# Electrics.net
KiCad netlist of a schematic drawn in EAGLE
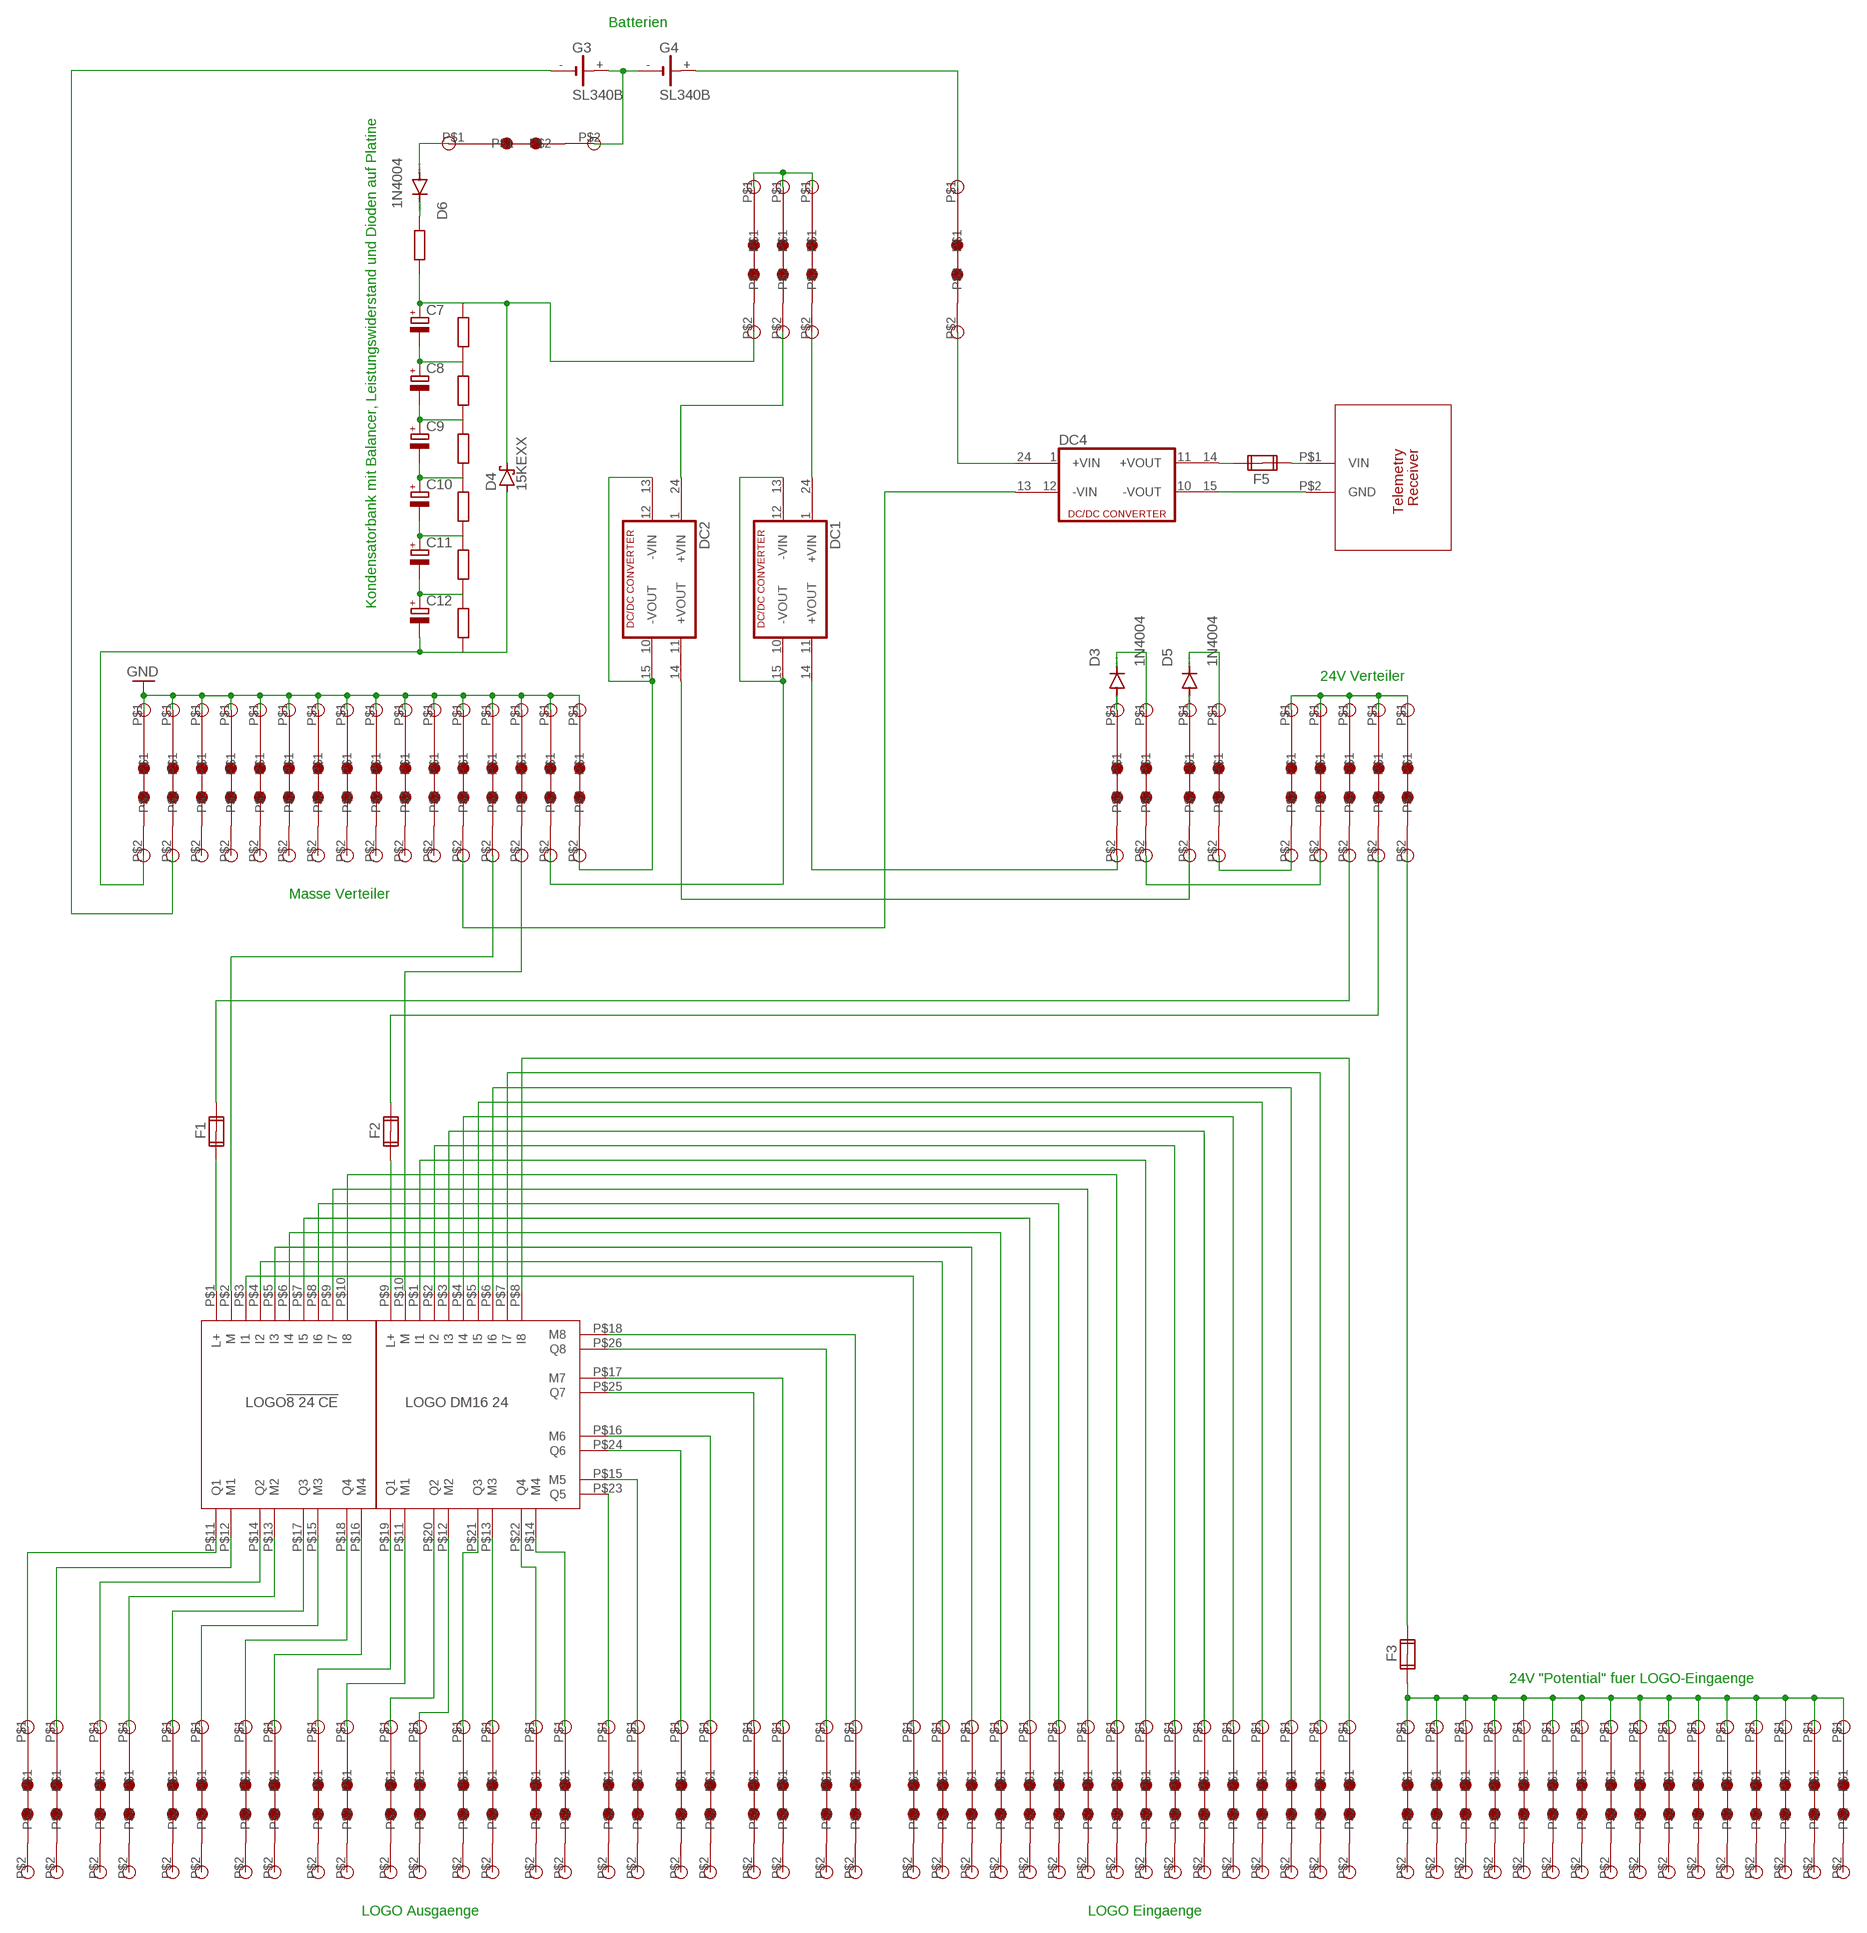
[diagram p0: schematic, sheet 1]

(export (version "E")
  (design (tool "Eeschema 10.0.6"))
  (components
    (comp (ref "C7")
      (value "CPOL-EU085CS-1AR")
      (footprint "eagle-import:085CS_1AR")
      (libsource (lib "eagle-import") (part "CPOL-EU085CS-1AR"))
    )
    (comp (ref "C8")
      (value "CPOL-EU085CS-1AR")
      (footprint "eagle-import:085CS_1AR")
      (libsource (lib "eagle-import") (part "CPOL-EU085CS-1AR"))
    )
    (comp (ref "C9")
      (value "CPOL-EU085CS-1AR")
      (footprint "eagle-import:085CS_1AR")
      (libsource (lib "eagle-import") (part "CPOL-EU085CS-1AR"))
    )
    (comp (ref "C10")
      (value "CPOL-EU085CS-1AR")
      (footprint "eagle-import:085CS_1AR")
      (libsource (lib "eagle-import") (part "CPOL-EU085CS-1AR"))
    )
    (comp (ref "C11")
      (value "CPOL-EU085CS-1AR")
      (footprint "eagle-import:085CS_1AR")
      (libsource (lib "eagle-import") (part "CPOL-EU085CS-1AR"))
    )
    (comp (ref "C12")
      (value "CPOL-EU085CS-1AR")
      (footprint "eagle-import:085CS_1AR")
      (libsource (lib "eagle-import") (part "CPOL-EU085CS-1AR"))
    )
    (comp (ref "D3")
      (value "1N4004")
      (footprint "eagle-import:DO41-10")
      (libsource (lib "eagle-import") (part "1N4004"))
    )
    (comp (ref "D4")
      (value "15KEXX")
      (footprint "eagle-import:CB429-17")
      (libsource (lib "eagle-import") (part "15KEXX"))
    )
    (comp (ref "D5")
      (value "1N4004")
      (footprint "eagle-import:DO41-10")
      (libsource (lib "eagle-import") (part "1N4004"))
    )
    (comp (ref "D6")
      (value "1N4004")
      (footprint "eagle-import:DO41-10")
      (libsource (lib "eagle-import") (part "1N4004"))
    )
    (comp (ref "DC1")
      (value "DC213R")
      (footprint "eagle-import:CMK")
      (libsource (lib "eagle-import") (part "DC213R"))
    )
    (comp (ref "DC2")
      (value "DC213R")
      (footprint "eagle-import:CMK")
      (libsource (lib "eagle-import") (part "DC213R"))
    )
    (comp (ref "DC4")
      (value "DC213R")
      (footprint "eagle-import:CMK")
      (libsource (lib "eagle-import") (part "DC213R"))
    )
    (comp (ref "F1")
      (value "FUSE2P")
      (footprint "eagle-import:FUSE1")
      (libsource (lib "eagle-import") (part "FUSE2P"))
    )
    (comp (ref "F2")
      (value "FUSE2P")
      (footprint "eagle-import:FUSE1")
      (libsource (lib "eagle-import") (part "FUSE2P"))
    )
    (comp (ref "F3")
      (value "FUSE2P")
      (footprint "eagle-import:FUSE1")
      (libsource (lib "eagle-import") (part "FUSE2P"))
    )
    (comp (ref "F5")
      (value "FUSE2P")
      (footprint "eagle-import:FUSE1")
      (libsource (lib "eagle-import") (part "FUSE2P"))
    )
    (comp (ref "G3")
      (value "SL340B")
      (footprint "eagle-import:SL-340_B3.6V")
      (libsource (lib "eagle-import") (part "SL340B"))
    )
    (comp (ref "G4")
      (value "SL340B")
      (footprint "eagle-import:SL-340_B3.6V")
      (libsource (lib "eagle-import") (part "SL340B"))
    )
    (comp (ref "U$1")
      (value "2_PIN_CONNENCTOR")
      (footprint "eagle-import:2_PIN_CONN")
      (libsource (lib "eagle-import") (part "2_PIN_CONNENCTOR"))
    )
    (comp (ref "U$2")
      (value "2_PIN_CONNENCTOR")
      (footprint "eagle-import:2_PIN_CONN")
      (libsource (lib "eagle-import") (part "2_PIN_CONNENCTOR"))
    )
    (comp (ref "U$3")
      (value "2_PIN_CONNENCTOR")
      (footprint "eagle-import:2_PIN_CONN")
      (libsource (lib "eagle-import") (part "2_PIN_CONNENCTOR"))
    )
    (comp (ref "U$4")
      (value "2_PIN_CONNENCTOR")
      (footprint "eagle-import:2_PIN_CONN")
      (libsource (lib "eagle-import") (part "2_PIN_CONNENCTOR"))
    )
    (comp (ref "U$5")
      (value "LOGO8_24_CE")
      (footprint "eagle-import:LOGO8_24_CE")
      (libsource (lib "eagle-import") (part "LOGO8_24_CE"))
    )
    (comp (ref "U$7")
      (value "LOGO_DM16_24")
      (footprint "eagle-import:LOGO_DM16_24")
      (libsource (lib "eagle-import") (part "LOGO_DM16_24"))
    )
    (comp (ref "U$8")
      (value "2_PIN_CONNENCTOR")
      (footprint "eagle-import:2_PIN_CONN")
      (libsource (lib "eagle-import") (part "2_PIN_CONNENCTOR"))
    )
    (comp (ref "U$9")
      (value "2_PIN_CONNENCTOR")
      (footprint "eagle-import:2_PIN_CONN")
      (libsource (lib "eagle-import") (part "2_PIN_CONNENCTOR"))
    )
    (comp (ref "U$10")
      (value "2_PIN_CONNENCTOR")
      (footprint "eagle-import:2_PIN_CONN")
      (libsource (lib "eagle-import") (part "2_PIN_CONNENCTOR"))
    )
    (comp (ref "U$11")
      (value "2_PIN_CONNENCTOR")
      (footprint "eagle-import:2_PIN_CONN")
      (libsource (lib "eagle-import") (part "2_PIN_CONNENCTOR"))
    )
    (comp (ref "U$12")
      (value "2_PIN_CONNENCTOR")
      (footprint "eagle-import:2_PIN_CONN")
      (libsource (lib "eagle-import") (part "2_PIN_CONNENCTOR"))
    )
    (comp (ref "U$13")
      (value "2_PIN_CONNENCTOR")
      (footprint "eagle-import:2_PIN_CONN")
      (libsource (lib "eagle-import") (part "2_PIN_CONNENCTOR"))
    )
    (comp (ref "U$14")
      (value "2_PIN_CONNENCTOR")
      (footprint "eagle-import:2_PIN_CONN")
      (libsource (lib "eagle-import") (part "2_PIN_CONNENCTOR"))
    )
    (comp (ref "U$15")
      (value "2_PIN_CONNENCTOR")
      (footprint "eagle-import:2_PIN_CONN")
      (libsource (lib "eagle-import") (part "2_PIN_CONNENCTOR"))
    )
    (comp (ref "U$16")
      (value "2_PIN_CONNENCTOR")
      (footprint "eagle-import:2_PIN_CONN")
      (libsource (lib "eagle-import") (part "2_PIN_CONNENCTOR"))
    )
    (comp (ref "U$17")
      (value "2_PIN_CONNENCTOR")
      (footprint "eagle-import:2_PIN_CONN")
      (libsource (lib "eagle-import") (part "2_PIN_CONNENCTOR"))
    )
    (comp (ref "U$18")
      (value "2_PIN_CONNENCTOR")
      (footprint "eagle-import:2_PIN_CONN")
      (libsource (lib "eagle-import") (part "2_PIN_CONNENCTOR"))
    )
    (comp (ref "U$19")
      (value "2_PIN_CONNENCTOR")
      (footprint "eagle-import:2_PIN_CONN")
      (libsource (lib "eagle-import") (part "2_PIN_CONNENCTOR"))
    )
    (comp (ref "U$20")
      (value "2_PIN_CONNENCTOR")
      (footprint "eagle-import:2_PIN_CONN")
      (libsource (lib "eagle-import") (part "2_PIN_CONNENCTOR"))
    )
    (comp (ref "U$21")
      (value "2_PIN_CONNENCTOR")
      (footprint "eagle-import:2_PIN_CONN")
      (libsource (lib "eagle-import") (part "2_PIN_CONNENCTOR"))
    )
    (comp (ref "U$22")
      (value "2_PIN_CONNENCTOR")
      (footprint "eagle-import:2_PIN_CONN")
      (libsource (lib "eagle-import") (part "2_PIN_CONNENCTOR"))
    )
    (comp (ref "U$23")
      (value "2_PIN_CONNENCTOR")
      (footprint "eagle-import:2_PIN_CONN")
      (libsource (lib "eagle-import") (part "2_PIN_CONNENCTOR"))
    )
    (comp (ref "U$24")
      (value "2_PIN_CONNENCTOR")
      (footprint "eagle-import:2_PIN_CONN")
      (libsource (lib "eagle-import") (part "2_PIN_CONNENCTOR"))
    )
    (comp (ref "U$25")
      (value "2_PIN_CONNENCTOR")
      (footprint "eagle-import:2_PIN_CONN")
      (libsource (lib "eagle-import") (part "2_PIN_CONNENCTOR"))
    )
    (comp (ref "U$26")
      (value "2_PIN_CONNENCTOR")
      (footprint "eagle-import:2_PIN_CONN")
      (libsource (lib "eagle-import") (part "2_PIN_CONNENCTOR"))
    )
    (comp (ref "U$27")
      (value "2_PIN_CONNENCTOR")
      (footprint "eagle-import:2_PIN_CONN")
      (libsource (lib "eagle-import") (part "2_PIN_CONNENCTOR"))
    )
    (comp (ref "U$28")
      (value "2_PIN_CONNENCTOR")
      (footprint "eagle-import:2_PIN_CONN")
      (libsource (lib "eagle-import") (part "2_PIN_CONNENCTOR"))
    )
    (comp (ref "U$29")
      (value "2_PIN_CONNENCTOR")
      (footprint "eagle-import:2_PIN_CONN")
      (libsource (lib "eagle-import") (part "2_PIN_CONNENCTOR"))
    )
    (comp (ref "U$30")
      (value "2_PIN_CONNENCTOR")
      (footprint "eagle-import:2_PIN_CONN")
      (libsource (lib "eagle-import") (part "2_PIN_CONNENCTOR"))
    )
    (comp (ref "U$31")
      (value "2_PIN_CONNENCTOR")
      (footprint "eagle-import:2_PIN_CONN")
      (libsource (lib "eagle-import") (part "2_PIN_CONNENCTOR"))
    )
    (comp (ref "U$32")
      (value "2_PIN_CONNENCTOR")
      (footprint "eagle-import:2_PIN_CONN")
      (libsource (lib "eagle-import") (part "2_PIN_CONNENCTOR"))
    )
    (comp (ref "U$33")
      (value "2_PIN_CONNENCTOR")
      (footprint "eagle-import:2_PIN_CONN")
      (libsource (lib "eagle-import") (part "2_PIN_CONNENCTOR"))
    )
    (comp (ref "U$34")
      (value "2_PIN_CONNENCTOR")
      (footprint "eagle-import:2_PIN_CONN")
      (libsource (lib "eagle-import") (part "2_PIN_CONNENCTOR"))
    )
    (comp (ref "U$35")
      (value "2_PIN_CONNENCTOR")
      (footprint "eagle-import:2_PIN_CONN")
      (libsource (lib "eagle-import") (part "2_PIN_CONNENCTOR"))
    )
    (comp (ref "U$36")
      (value "2_PIN_CONNENCTOR")
      (footprint "eagle-import:2_PIN_CONN")
      (libsource (lib "eagle-import") (part "2_PIN_CONNENCTOR"))
    )
    (comp (ref "U$37")
      (value "2_PIN_CONNENCTOR")
      (footprint "eagle-import:2_PIN_CONN")
      (libsource (lib "eagle-import") (part "2_PIN_CONNENCTOR"))
    )
    (comp (ref "U$38")
      (value "2_PIN_CONNENCTOR")
      (footprint "eagle-import:2_PIN_CONN")
      (libsource (lib "eagle-import") (part "2_PIN_CONNENCTOR"))
    )
    (comp (ref "U$39")
      (value "2_PIN_CONNENCTOR")
      (footprint "eagle-import:2_PIN_CONN")
      (libsource (lib "eagle-import") (part "2_PIN_CONNENCTOR"))
    )
    (comp (ref "U$40")
      (value "2_PIN_CONNENCTOR")
      (footprint "eagle-import:2_PIN_CONN")
      (libsource (lib "eagle-import") (part "2_PIN_CONNENCTOR"))
    )
    (comp (ref "U$41")
      (value "2_PIN_CONNENCTOR")
      (footprint "eagle-import:2_PIN_CONN")
      (libsource (lib "eagle-import") (part "2_PIN_CONNENCTOR"))
    )
    (comp (ref "U$42")
      (value "2_PIN_CONNENCTOR")
      (footprint "eagle-import:2_PIN_CONN")
      (libsource (lib "eagle-import") (part "2_PIN_CONNENCTOR"))
    )
    (comp (ref "U$43")
      (value "2_PIN_CONNENCTOR")
      (footprint "eagle-import:2_PIN_CONN")
      (libsource (lib "eagle-import") (part "2_PIN_CONNENCTOR"))
    )
    (comp (ref "U$44")
      (value "2_PIN_CONNENCTOR")
      (footprint "eagle-import:2_PIN_CONN")
      (libsource (lib "eagle-import") (part "2_PIN_CONNENCTOR"))
    )
    (comp (ref "U$45")
      (value "2_PIN_CONNENCTOR")
      (footprint "eagle-import:2_PIN_CONN")
      (libsource (lib "eagle-import") (part "2_PIN_CONNENCTOR"))
    )
    (comp (ref "U$46")
      (value "2_PIN_CONNENCTOR")
      (footprint "eagle-import:2_PIN_CONN")
      (libsource (lib "eagle-import") (part "2_PIN_CONNENCTOR"))
    )
    (comp (ref "U$47")
      (value "2_PIN_CONNENCTOR")
      (footprint "eagle-import:2_PIN_CONN")
      (libsource (lib "eagle-import") (part "2_PIN_CONNENCTOR"))
    )
    (comp (ref "U$48")
      (value "2_PIN_CONNENCTOR")
      (footprint "eagle-import:2_PIN_CONN")
      (libsource (lib "eagle-import") (part "2_PIN_CONNENCTOR"))
    )
    (comp (ref "U$49")
      (value "2_PIN_CONNENCTOR")
      (footprint "eagle-import:2_PIN_CONN")
      (libsource (lib "eagle-import") (part "2_PIN_CONNENCTOR"))
    )
    (comp (ref "U$50")
      (value "2_PIN_CONNENCTOR")
      (footprint "eagle-import:2_PIN_CONN")
      (libsource (lib "eagle-import") (part "2_PIN_CONNENCTOR"))
    )
    (comp (ref "U$51")
      (value "2_PIN_CONNENCTOR")
      (footprint "eagle-import:2_PIN_CONN")
      (libsource (lib "eagle-import") (part "2_PIN_CONNENCTOR"))
    )
    (comp (ref "U$52")
      (value "2_PIN_CONNENCTOR")
      (footprint "eagle-import:2_PIN_CONN")
      (libsource (lib "eagle-import") (part "2_PIN_CONNENCTOR"))
    )
    (comp (ref "U$53")
      (value "2_PIN_CONNENCTOR")
      (footprint "eagle-import:2_PIN_CONN")
      (libsource (lib "eagle-import") (part "2_PIN_CONNENCTOR"))
    )
    (comp (ref "U$54")
      (value "2_PIN_CONNENCTOR")
      (footprint "eagle-import:2_PIN_CONN")
      (libsource (lib "eagle-import") (part "2_PIN_CONNENCTOR"))
    )
    (comp (ref "U$55")
      (value "2_PIN_CONNENCTOR")
      (footprint "eagle-import:2_PIN_CONN")
      (libsource (lib "eagle-import") (part "2_PIN_CONNENCTOR"))
    )
    (comp (ref "U$56")
      (value "2_PIN_CONNENCTOR")
      (footprint "eagle-import:2_PIN_CONN")
      (libsource (lib "eagle-import") (part "2_PIN_CONNENCTOR"))
    )
    (comp (ref "U$57")
      (value "2_PIN_CONNENCTOR")
      (footprint "eagle-import:2_PIN_CONN")
      (libsource (lib "eagle-import") (part "2_PIN_CONNENCTOR"))
    )
    (comp (ref "U$58")
      (value "2_PIN_CONNENCTOR")
      (footprint "eagle-import:2_PIN_CONN")
      (libsource (lib "eagle-import") (part "2_PIN_CONNENCTOR"))
    )
    (comp (ref "U$59")
      (value "2_PIN_CONNENCTOR")
      (footprint "eagle-import:2_PIN_CONN")
      (libsource (lib "eagle-import") (part "2_PIN_CONNENCTOR"))
    )
    (comp (ref "U$60")
      (value "2_PIN_CONNENCTOR")
      (footprint "eagle-import:2_PIN_CONN")
      (libsource (lib "eagle-import") (part "2_PIN_CONNENCTOR"))
    )
    (comp (ref "U$61")
      (value "2_PIN_CONNENCTOR")
      (footprint "eagle-import:2_PIN_CONN")
      (libsource (lib "eagle-import") (part "2_PIN_CONNENCTOR"))
    )
    (comp (ref "U$62")
      (value "2_PIN_CONNENCTOR")
      (footprint "eagle-import:2_PIN_CONN")
      (libsource (lib "eagle-import") (part "2_PIN_CONNENCTOR"))
    )
    (comp (ref "U$63")
      (value "2_PIN_CONNENCTOR")
      (footprint "eagle-import:2_PIN_CONN")
      (libsource (lib "eagle-import") (part "2_PIN_CONNENCTOR"))
    )
    (comp (ref "U$64")
      (value "2_PIN_CONNENCTOR")
      (footprint "eagle-import:2_PIN_CONN")
      (libsource (lib "eagle-import") (part "2_PIN_CONNENCTOR"))
    )
    (comp (ref "U$65")
      (value "2_PIN_CONNENCTOR")
      (footprint "eagle-import:2_PIN_CONN")
      (libsource (lib "eagle-import") (part "2_PIN_CONNENCTOR"))
    )
    (comp (ref "U$66")
      (value "2_PIN_CONNENCTOR")
      (footprint "eagle-import:2_PIN_CONN")
      (libsource (lib "eagle-import") (part "2_PIN_CONNENCTOR"))
    )
    (comp (ref "U$67")
      (value "2_PIN_CONNENCTOR")
      (footprint "eagle-import:2_PIN_CONN")
      (libsource (lib "eagle-import") (part "2_PIN_CONNENCTOR"))
    )
    (comp (ref "U$68")
      (value "2_PIN_CONNENCTOR")
      (footprint "eagle-import:2_PIN_CONN")
      (libsource (lib "eagle-import") (part "2_PIN_CONNENCTOR"))
    )
    (comp (ref "U$69")
      (value "2_PIN_CONNENCTOR")
      (footprint "eagle-import:2_PIN_CONN")
      (libsource (lib "eagle-import") (part "2_PIN_CONNENCTOR"))
    )
    (comp (ref "U$70")
      (value "2_PIN_CONNENCTOR")
      (footprint "eagle-import:2_PIN_CONN")
      (libsource (lib "eagle-import") (part "2_PIN_CONNENCTOR"))
    )
    (comp (ref "U$71")
      (value "2_PIN_CONNENCTOR")
      (footprint "eagle-import:2_PIN_CONN")
      (libsource (lib "eagle-import") (part "2_PIN_CONNENCTOR"))
    )
    (comp (ref "U$72")
      (value "2_PIN_CONNENCTOR")
      (footprint "eagle-import:2_PIN_CONN")
      (libsource (lib "eagle-import") (part "2_PIN_CONNENCTOR"))
    )
    (comp (ref "U$73")
      (value "2_PIN_CONNENCTOR")
      (footprint "eagle-import:2_PIN_CONN")
      (libsource (lib "eagle-import") (part "2_PIN_CONNENCTOR"))
    )
    (comp (ref "U$74")
      (value "2_PIN_CONNENCTOR")
      (footprint "eagle-import:2_PIN_CONN")
      (libsource (lib "eagle-import") (part "2_PIN_CONNENCTOR"))
    )
    (comp (ref "U$75")
      (value "2_PIN_CONNENCTOR")
      (footprint "eagle-import:2_PIN_CONN")
      (libsource (lib "eagle-import") (part "2_PIN_CONNENCTOR"))
    )
    (comp (ref "U$76")
      (value "2_PIN_CONNENCTOR")
      (footprint "eagle-import:2_PIN_CONN")
      (libsource (lib "eagle-import") (part "2_PIN_CONNENCTOR"))
    )
    (comp (ref "U$77")
      (value "2_PIN_CONNENCTOR")
      (footprint "eagle-import:2_PIN_CONN")
      (libsource (lib "eagle-import") (part "2_PIN_CONNENCTOR"))
    )
    (comp (ref "U$78")
      (value "2_PIN_CONNENCTOR")
      (footprint "eagle-import:2_PIN_CONN")
      (libsource (lib "eagle-import") (part "2_PIN_CONNENCTOR"))
    )
    (comp (ref "U$79")
      (value "2_PIN_CONNENCTOR")
      (footprint "eagle-import:2_PIN_CONN")
      (libsource (lib "eagle-import") (part "2_PIN_CONNENCTOR"))
    )
    (comp (ref "U$80")
      (value "2_PIN_CONNENCTOR")
      (footprint "eagle-import:2_PIN_CONN")
      (libsource (lib "eagle-import") (part "2_PIN_CONNENCTOR"))
    )
    (comp (ref "U$81")
      (value "2_PIN_CONNENCTOR")
      (footprint "eagle-import:2_PIN_CONN")
      (libsource (lib "eagle-import") (part "2_PIN_CONNENCTOR"))
    )
    (comp (ref "U$82")
      (value "2_PIN_CONNENCTOR")
      (footprint "eagle-import:2_PIN_CONN")
      (libsource (lib "eagle-import") (part "2_PIN_CONNENCTOR"))
    )
    (comp (ref "U$83")
      (value "2_PIN_CONNENCTOR")
      (footprint "eagle-import:2_PIN_CONN")
      (libsource (lib "eagle-import") (part "2_PIN_CONNENCTOR"))
    )
    (comp (ref "U$84")
      (value "2_PIN_CONNENCTOR")
      (footprint "eagle-import:2_PIN_CONN")
      (libsource (lib "eagle-import") (part "2_PIN_CONNENCTOR"))
    )
    (comp (ref "U$85")
      (value "2_PIN_CONNENCTOR")
      (footprint "eagle-import:2_PIN_CONN")
      (libsource (lib "eagle-import") (part "2_PIN_CONNENCTOR"))
    )
    (comp (ref "U$86")
      (value "2_PIN_CONNENCTOR")
      (footprint "eagle-import:2_PIN_CONN")
      (libsource (lib "eagle-import") (part "2_PIN_CONNENCTOR"))
    )
    (comp (ref "U$87")
      (value "2_PIN_CONNENCTOR")
      (footprint "eagle-import:2_PIN_CONN")
      (libsource (lib "eagle-import") (part "2_PIN_CONNENCTOR"))
    )
    (comp (ref "U$89")
      (value "2_PIN_CONNENCTOR")
      (footprint "eagle-import:2_PIN_CONN")
      (libsource (lib "eagle-import") (part "2_PIN_CONNENCTOR"))
    )
    (comp (ref "U$90")
      (value "TELEMETRY_RECEIVER")
      (footprint "eagle-import:TELEMETRY_RECEIVER")
      (libsource (lib "eagle-import") (part "TELEMETRY_RECEIVER"))
    )
    (comp (ref "U$91")
      (value "2_PIN_CONNENCTOR")
      (footprint "eagle-import:2_PIN_CONN")
      (libsource (lib "eagle-import") (part "2_PIN_CONNENCTOR"))
    )
  )
  (nets
    (net (code "1") (name "GND") (class "Default")
      (node (ref "U$69") (pin "P$1") (pinfunction "P$1_P$1") (pintype "bidirectional"))
      (node (ref "U$70") (pin "P$1") (pinfunction "P$1_P$1") (pintype "bidirectional"))
      (node (ref "U$71") (pin "P$1") (pinfunction "P$1_P$1") (pintype "bidirectional"))
      (node (ref "U$72") (pin "P$1") (pinfunction "P$1_P$1") (pintype "bidirectional"))
      (node (ref "U$73") (pin "P$1") (pinfunction "P$1_P$1") (pintype "bidirectional"))
      (node (ref "U$74") (pin "P$1") (pinfunction "P$1_P$1") (pintype "bidirectional"))
      (node (ref "U$75") (pin "P$1") (pinfunction "P$1_P$1") (pintype "bidirectional"))
      (node (ref "U$76") (pin "P$1") (pinfunction "P$1_P$1") (pintype "bidirectional"))
      (node (ref "U$77") (pin "P$1") (pinfunction "P$1_P$1") (pintype "bidirectional"))
      (node (ref "U$78") (pin "P$1") (pinfunction "P$1_P$1") (pintype "bidirectional"))
      (node (ref "U$79") (pin "P$1") (pinfunction "P$1_P$1") (pintype "bidirectional"))
      (node (ref "U$80") (pin "P$1") (pinfunction "P$1_P$1") (pintype "bidirectional"))
      (node (ref "U$81") (pin "P$1") (pinfunction "P$1_P$1") (pintype "bidirectional"))
      (node (ref "U$82") (pin "P$1") (pinfunction "P$1_P$1") (pintype "bidirectional"))
      (node (ref "U$83") (pin "P$1") (pinfunction "P$1_P$1") (pintype "bidirectional"))
      (node (ref "U$84") (pin "P$1") (pinfunction "P$1_P$1") (pintype "bidirectional"))
    )
    (net (code "2") (name "Net-(C7-Pad+)") (class "Default")
      (node (ref "C7") (pin "+") (pinfunction "+_+") (pintype "passive"))
      (node (ref "D4") (pin "C") (pinfunction "C_C") (pintype "passive"))
      (node (ref "U$85") (pin "P$2") (pinfunction "P$2_P$2") (pintype "bidirectional"))
    )
    (net (code "3") (name "Net-(C7-Pad-)") (class "Default")
      (node (ref "C7") (pin "-") (pinfunction "-_-") (pintype "passive"))
      (node (ref "C8") (pin "+") (pinfunction "+_+") (pintype "passive"))
    )
    (net (code "4") (name "Net-(C8-Pad-)") (class "Default")
      (node (ref "C8") (pin "-") (pinfunction "-_-") (pintype "passive"))
      (node (ref "C9") (pin "+") (pinfunction "+_+") (pintype "passive"))
    )
    (net (code "5") (name "Net-(C10-Pad+)") (class "Default")
      (node (ref "C10") (pin "+") (pinfunction "+_+") (pintype "passive"))
      (node (ref "C9") (pin "-") (pinfunction "-_-") (pintype "passive"))
    )
    (net (code "6") (name "Net-(C10-Pad-)") (class "Default")
      (node (ref "C10") (pin "-") (pinfunction "-_-") (pintype "passive"))
      (node (ref "C11") (pin "+") (pinfunction "+_+") (pintype "passive"))
    )
    (net (code "7") (name "Net-(C11-Pad-)") (class "Default")
      (node (ref "C11") (pin "-") (pinfunction "-_-") (pintype "passive"))
      (node (ref "C12") (pin "+") (pinfunction "+_+") (pintype "passive"))
    )
    (net (code "8") (name "Net-(C12-Pad-)") (class "Default")
      (node (ref "C12") (pin "-") (pinfunction "-_-") (pintype "passive"))
      (node (ref "D4") (pin "A") (pinfunction "A_A") (pintype "passive"))
      (node (ref "U$69") (pin "P$2") (pinfunction "P$2_P$2") (pintype "bidirectional"))
    )
    (net (code "9") (name "Net-(D3-PadA)") (class "Default")
      (node (ref "D3") (pin "A") (pinfunction "A_A") (pintype "passive"))
      (node (ref "U$65") (pin "P$1") (pinfunction "P$1_P$1") (pintype "bidirectional"))
    )
    (net (code "10") (name "Net-(D3-PadC)") (class "Default")
      (node (ref "D3") (pin "C") (pinfunction "C_C") (pintype "passive"))
      (node (ref "U$66") (pin "P$1") (pinfunction "P$1_P$1") (pintype "bidirectional"))
    )
    (net (code "11") (name "Net-(D5-PadA)") (class "Default")
      (node (ref "D5") (pin "A") (pinfunction "A_A") (pintype "passive"))
      (node (ref "U$67") (pin "P$1") (pinfunction "P$1_P$1") (pintype "bidirectional"))
    )
    (net (code "12") (name "Net-(D5-PadC)") (class "Default")
      (node (ref "D5") (pin "C") (pinfunction "C_C") (pintype "passive"))
      (node (ref "U$68") (pin "P$1") (pinfunction "P$1_P$1") (pintype "bidirectional"))
    )
    (net (code "13") (name "Net-(D6-PadA)") (class "Default")
      (node (ref "D6") (pin "A") (pinfunction "A_A") (pintype "passive"))
      (node (ref "U$91") (pin "P$1") (pinfunction "P$1_P$1") (pintype "bidirectional"))
    )
    (net (code "14") (name "Net-(DC1-+VIN1)") (class "Default")
      (node (ref "DC1") (pin "24") (pinfunction "+VIN1_24") (pintype "passive"))
      (node (ref "U$87") (pin "P$2") (pinfunction "P$2_P$2") (pintype "bidirectional"))
    )
    (net (code "15") (name "Net-(DC1-+VOUT1)") (class "Default")
      (node (ref "DC1") (pin "14") (pinfunction "+VOUT1_14") (pintype "passive"))
      (node (ref "U$65") (pin "P$2") (pinfunction "P$2_P$2") (pintype "bidirectional"))
    )
    (net (code "16") (name "Net-(DC1--VIN1)") (class "Default")
      (node (ref "DC1") (pin "13") (pinfunction "-VIN1_13") (pintype "passive"))
      (node (ref "DC1") (pin "15") (pinfunction "-VOUT1_15") (pintype "passive"))
      (node (ref "U$83") (pin "P$2") (pinfunction "P$2_P$2") (pintype "bidirectional"))
    )
    (net (code "17") (name "Net-(DC2-+VIN1)") (class "Default")
      (node (ref "DC2") (pin "24") (pinfunction "+VIN1_24") (pintype "passive"))
      (node (ref "U$86") (pin "P$2") (pinfunction "P$2_P$2") (pintype "bidirectional"))
    )
    (net (code "18") (name "Net-(DC2-+VOUT1)") (class "Default")
      (node (ref "DC2") (pin "14") (pinfunction "+VOUT1_14") (pintype "passive"))
      (node (ref "U$67") (pin "P$2") (pinfunction "P$2_P$2") (pintype "bidirectional"))
    )
    (net (code "19") (name "Net-(DC2--VIN1)") (class "Default")
      (node (ref "DC2") (pin "13") (pinfunction "-VIN1_13") (pintype "passive"))
      (node (ref "DC2") (pin "15") (pinfunction "-VOUT1_15") (pintype "passive"))
      (node (ref "U$84") (pin "P$2") (pinfunction "P$2_P$2") (pintype "bidirectional"))
    )
    (net (code "20") (name "Net-(DC4-+VIN1)") (class "Default")
      (node (ref "DC4") (pin "24") (pinfunction "+VIN1_24") (pintype "passive"))
      (node (ref "U$89") (pin "P$2") (pinfunction "P$2_P$2") (pintype "bidirectional"))
    )
    (net (code "21") (name "Net-(DC4-+VOUT1)") (class "Default")
      (node (ref "DC4") (pin "14") (pinfunction "+VOUT1_14") (pintype "passive"))
      (node (ref "F5") (pin "2A") (pinfunction "2A_2A") (pintype "passive"))
    )
    (net (code "22") (name "Net-(DC4--VIN1)") (class "Default")
      (node (ref "DC4") (pin "13") (pinfunction "-VIN1_13") (pintype "passive"))
      (node (ref "U$80") (pin "P$2") (pinfunction "P$2_P$2") (pintype "bidirectional"))
    )
    (net (code "23") (name "Net-(DC4--VOUT1)") (class "Default")
      (node (ref "DC4") (pin "15") (pinfunction "-VOUT1_15") (pintype "passive"))
      (node (ref "U$90") (pin "P$2") (pinfunction "GND_P$2") (pintype "bidirectional"))
    )
    (net (code "24") (name "Net-(F1-Pad2A)") (class "Default")
      (node (ref "F1") (pin "2A") (pinfunction "2A_2A") (pintype "passive"))
      (node (ref "U$62") (pin "P$2") (pinfunction "P$2_P$2") (pintype "bidirectional"))
    )
    (net (code "25") (name "Net-(F2-Pad2A)") (class "Default")
      (node (ref "F2") (pin "2A") (pinfunction "2A_2A") (pintype "passive"))
      (node (ref "U$63") (pin "P$2") (pinfunction "P$2_P$2") (pintype "bidirectional"))
    )
    (net (code "26") (name "Net-(F3-Pad1A)") (class "Default")
      (node (ref "F3") (pin "1A") (pinfunction "1A_1A") (pintype "passive"))
      (node (ref "U$44") (pin "P$1") (pinfunction "P$1_P$1") (pintype "bidirectional"))
      (node (ref "U$45") (pin "P$1") (pinfunction "P$1_P$1") (pintype "bidirectional"))
      (node (ref "U$46") (pin "P$1") (pinfunction "P$1_P$1") (pintype "bidirectional"))
      (node (ref "U$47") (pin "P$1") (pinfunction "P$1_P$1") (pintype "bidirectional"))
      (node (ref "U$48") (pin "P$1") (pinfunction "P$1_P$1") (pintype "bidirectional"))
      (node (ref "U$49") (pin "P$1") (pinfunction "P$1_P$1") (pintype "bidirectional"))
      (node (ref "U$50") (pin "P$1") (pinfunction "P$1_P$1") (pintype "bidirectional"))
      (node (ref "U$51") (pin "P$1") (pinfunction "P$1_P$1") (pintype "bidirectional"))
      (node (ref "U$52") (pin "P$1") (pinfunction "P$1_P$1") (pintype "bidirectional"))
      (node (ref "U$53") (pin "P$1") (pinfunction "P$1_P$1") (pintype "bidirectional"))
      (node (ref "U$54") (pin "P$1") (pinfunction "P$1_P$1") (pintype "bidirectional"))
      (node (ref "U$55") (pin "P$1") (pinfunction "P$1_P$1") (pintype "bidirectional"))
      (node (ref "U$56") (pin "P$1") (pinfunction "P$1_P$1") (pintype "bidirectional"))
      (node (ref "U$57") (pin "P$1") (pinfunction "P$1_P$1") (pintype "bidirectional"))
      (node (ref "U$58") (pin "P$1") (pinfunction "P$1_P$1") (pintype "bidirectional"))
      (node (ref "U$59") (pin "P$1") (pinfunction "P$1_P$1") (pintype "bidirectional"))
    )
    (net (code "27") (name "Net-(F3-Pad2A)") (class "Default")
      (node (ref "F3") (pin "2A") (pinfunction "2A_2A") (pintype "passive"))
      (node (ref "U$64") (pin "P$2") (pinfunction "P$2_P$2") (pintype "bidirectional"))
    )
    (net (code "28") (name "Net-(G3-Pad+)") (class "Default")
      (node (ref "G3") (pin "+") (pinfunction "+_+") (pintype "passive"))
      (node (ref "G4") (pin "-") (pinfunction "-_-") (pintype "passive"))
      (node (ref "U$91") (pin "P$2") (pinfunction "P$2_P$2") (pintype "bidirectional"))
    )
    (net (code "29") (name "Net-(G3-Pad-)") (class "Default")
      (node (ref "G3") (pin "-") (pinfunction "-_-") (pintype "passive"))
      (node (ref "U$70") (pin "P$2") (pinfunction "P$2_P$2") (pintype "bidirectional"))
    )
    (net (code "30") (name "Net-(G4-Pad+)") (class "Default")
      (node (ref "G4") (pin "+") (pinfunction "+_+") (pintype "passive"))
      (node (ref "U$89") (pin "P$1") (pinfunction "P$1_P$1") (pintype "bidirectional"))
    )
    (net (code "31") (name "Net-(U$5-I1)") (class "Default")
      (node (ref "U$28") (pin "P$1") (pinfunction "P$1_P$1") (pintype "bidirectional"))
      (node (ref "U$5") (pin "P$3") (pinfunction "I1_P$3") (pintype "input"))
    )
    (net (code "32") (name "Net-(U$5-I2)") (class "Default")
      (node (ref "U$29") (pin "P$1") (pinfunction "P$1_P$1") (pintype "bidirectional"))
      (node (ref "U$5") (pin "P$4") (pinfunction "I2_P$4") (pintype "input"))
    )
    (net (code "33") (name "Net-(U$5-I3)") (class "Default")
      (node (ref "U$30") (pin "P$1") (pinfunction "P$1_P$1") (pintype "bidirectional"))
      (node (ref "U$5") (pin "P$5") (pinfunction "I3_P$5") (pintype "input"))
    )
    (net (code "34") (name "Net-(U$5-I4)") (class "Default")
      (node (ref "U$31") (pin "P$1") (pinfunction "P$1_P$1") (pintype "bidirectional"))
      (node (ref "U$5") (pin "P$6") (pinfunction "I4_P$6") (pintype "input"))
    )
    (net (code "35") (name "Net-(U$5-I5)") (class "Default")
      (node (ref "U$32") (pin "P$1") (pinfunction "P$1_P$1") (pintype "bidirectional"))
      (node (ref "U$5") (pin "P$7") (pinfunction "I5_P$7") (pintype "input"))
    )
    (net (code "36") (name "Net-(U$5-I6)") (class "Default")
      (node (ref "U$33") (pin "P$1") (pinfunction "P$1_P$1") (pintype "bidirectional"))
      (node (ref "U$5") (pin "P$8") (pinfunction "I6_P$8") (pintype "input"))
    )
    (net (code "37") (name "Net-(U$5-I7)") (class "Default")
      (node (ref "U$34") (pin "P$1") (pinfunction "P$1_P$1") (pintype "bidirectional"))
      (node (ref "U$5") (pin "P$9") (pinfunction "I7_P$9") (pintype "input"))
    )
    (net (code "38") (name "Net-(U$5-I8)") (class "Default")
      (node (ref "U$35") (pin "P$1") (pinfunction "P$1_P$1") (pintype "bidirectional"))
      (node (ref "U$5") (pin "P$10") (pinfunction "I8_P$10") (pintype "input"))
    )
    (net (code "39") (name "Net-(U$5-L+)") (class "Default")
      (node (ref "F1") (pin "1A") (pinfunction "1A_1A") (pintype "passive"))
      (node (ref "U$5") (pin "P$1") (pinfunction "L+_P$1") (pintype "input"))
    )
    (net (code "40") (name "Net-(U$5-M)") (class "Default")
      (node (ref "U$5") (pin "P$2") (pinfunction "M_P$2") (pintype "input"))
      (node (ref "U$81") (pin "P$2") (pinfunction "P$2_P$2") (pintype "bidirectional"))
    )
    (net (code "41") (name "Net-(U$5-M1)") (class "Default")
      (node (ref "U$2") (pin "P$1") (pinfunction "P$1_P$1") (pintype "bidirectional"))
      (node (ref "U$5") (pin "P$12") (pinfunction "M1_P$12") (pintype "output"))
    )
    (net (code "42") (name "Net-(U$5-M2)") (class "Default")
      (node (ref "U$4") (pin "P$1") (pinfunction "P$1_P$1") (pintype "bidirectional"))
      (node (ref "U$5") (pin "P$13") (pinfunction "M2_P$13") (pintype "output"))
    )
    (net (code "43") (name "Net-(U$5-M3)") (class "Default")
      (node (ref "U$5") (pin "P$15") (pinfunction "M3_P$15") (pintype "output"))
      (node (ref "U$9") (pin "P$1") (pinfunction "P$1_P$1") (pintype "bidirectional"))
    )
    (net (code "44") (name "Net-(U$5-M4)") (class "Default")
      (node (ref "U$11") (pin "P$1") (pinfunction "P$1_P$1") (pintype "bidirectional"))
      (node (ref "U$5") (pin "P$16") (pinfunction "M4_P$16") (pintype "output"))
    )
    (net (code "45") (name "Net-(U$5-Q1)") (class "Default")
      (node (ref "U$1") (pin "P$1") (pinfunction "P$1_P$1") (pintype "bidirectional"))
      (node (ref "U$5") (pin "P$11") (pinfunction "Q1_P$11") (pintype "output"))
    )
    (net (code "46") (name "Net-(U$5-Q2)") (class "Default")
      (node (ref "U$3") (pin "P$1") (pinfunction "P$1_P$1") (pintype "bidirectional"))
      (node (ref "U$5") (pin "P$14") (pinfunction "Q2_P$14") (pintype "output"))
    )
    (net (code "47") (name "Net-(U$5-Q3)") (class "Default")
      (node (ref "U$5") (pin "P$17") (pinfunction "Q3_P$17") (pintype "output"))
      (node (ref "U$8") (pin "P$1") (pinfunction "P$1_P$1") (pintype "bidirectional"))
    )
    (net (code "48") (name "Net-(U$5-Q4)") (class "Default")
      (node (ref "U$10") (pin "P$1") (pinfunction "P$1_P$1") (pintype "bidirectional"))
      (node (ref "U$5") (pin "P$18") (pinfunction "Q4_P$18") (pintype "output"))
    )
    (net (code "49") (name "Net-(U$7-I1)") (class "Default")
      (node (ref "U$36") (pin "P$1") (pinfunction "P$1_P$1") (pintype "bidirectional"))
      (node (ref "U$7") (pin "P$1") (pinfunction "I1_P$1") (pintype "bidirectional"))
    )
    (net (code "50") (name "Net-(U$7-I2)") (class "Default")
      (node (ref "U$37") (pin "P$1") (pinfunction "P$1_P$1") (pintype "bidirectional"))
      (node (ref "U$7") (pin "P$2") (pinfunction "I2_P$2") (pintype "bidirectional"))
    )
    (net (code "51") (name "Net-(U$7-I3)") (class "Default")
      (node (ref "U$38") (pin "P$1") (pinfunction "P$1_P$1") (pintype "bidirectional"))
      (node (ref "U$7") (pin "P$3") (pinfunction "I3_P$3") (pintype "bidirectional"))
    )
    (net (code "52") (name "Net-(U$7-I4)") (class "Default")
      (node (ref "U$39") (pin "P$1") (pinfunction "P$1_P$1") (pintype "bidirectional"))
      (node (ref "U$7") (pin "P$4") (pinfunction "I4_P$4") (pintype "bidirectional"))
    )
    (net (code "53") (name "Net-(U$7-I5)") (class "Default")
      (node (ref "U$40") (pin "P$1") (pinfunction "P$1_P$1") (pintype "bidirectional"))
      (node (ref "U$7") (pin "P$5") (pinfunction "I5_P$5") (pintype "bidirectional"))
    )
    (net (code "54") (name "Net-(U$7-I6)") (class "Default")
      (node (ref "U$41") (pin "P$1") (pinfunction "P$1_P$1") (pintype "bidirectional"))
      (node (ref "U$7") (pin "P$6") (pinfunction "I6_P$6") (pintype "bidirectional"))
    )
    (net (code "55") (name "Net-(U$7-I7)") (class "Default")
      (node (ref "U$42") (pin "P$1") (pinfunction "P$1_P$1") (pintype "bidirectional"))
      (node (ref "U$7") (pin "P$7") (pinfunction "I7_P$7") (pintype "bidirectional"))
    )
    (net (code "56") (name "Net-(U$7-I8)") (class "Default")
      (node (ref "U$43") (pin "P$1") (pinfunction "P$1_P$1") (pintype "bidirectional"))
      (node (ref "U$7") (pin "P$8") (pinfunction "I8_P$8") (pintype "bidirectional"))
    )
    (net (code "57") (name "Net-(U$7-L+)") (class "Default")
      (node (ref "F2") (pin "1A") (pinfunction "1A_1A") (pintype "passive"))
      (node (ref "U$7") (pin "P$9") (pinfunction "L+_P$9") (pintype "bidirectional"))
    )
    (net (code "58") (name "Net-(U$7-M)") (class "Default")
      (node (ref "U$7") (pin "P$10") (pinfunction "M_P$10") (pintype "bidirectional"))
      (node (ref "U$82") (pin "P$2") (pinfunction "P$2_P$2") (pintype "bidirectional"))
    )
    (net (code "59") (name "Net-(U$7-M1)") (class "Default")
      (node (ref "U$13") (pin "P$1") (pinfunction "P$1_P$1") (pintype "bidirectional"))
      (node (ref "U$7") (pin "P$11") (pinfunction "M1_P$11") (pintype "bidirectional"))
    )
    (net (code "60") (name "Net-(U$7-M2)") (class "Default")
      (node (ref "U$15") (pin "P$1") (pinfunction "P$1_P$1") (pintype "bidirectional"))
      (node (ref "U$7") (pin "P$12") (pinfunction "M2_P$12") (pintype "bidirectional"))
    )
    (net (code "61") (name "Net-(U$7-M3)") (class "Default")
      (node (ref "U$17") (pin "P$1") (pinfunction "P$1_P$1") (pintype "bidirectional"))
      (node (ref "U$7") (pin "P$13") (pinfunction "M3_P$13") (pintype "bidirectional"))
    )
    (net (code "62") (name "Net-(U$7-M4)") (class "Default")
      (node (ref "U$19") (pin "P$1") (pinfunction "P$1_P$1") (pintype "bidirectional"))
      (node (ref "U$7") (pin "P$14") (pinfunction "M4_P$14") (pintype "bidirectional"))
    )
    (net (code "63") (name "Net-(U$7-M5)") (class "Default")
      (node (ref "U$21") (pin "P$1") (pinfunction "P$1_P$1") (pintype "bidirectional"))
      (node (ref "U$7") (pin "P$15") (pinfunction "M5_P$15") (pintype "bidirectional"))
    )
    (net (code "64") (name "Net-(U$7-M6)") (class "Default")
      (node (ref "U$23") (pin "P$1") (pinfunction "P$1_P$1") (pintype "bidirectional"))
      (node (ref "U$7") (pin "P$16") (pinfunction "M6_P$16") (pintype "bidirectional"))
    )
    (net (code "65") (name "Net-(U$7-M7)") (class "Default")
      (node (ref "U$25") (pin "P$1") (pinfunction "P$1_P$1") (pintype "bidirectional"))
      (node (ref "U$7") (pin "P$17") (pinfunction "M7_P$17") (pintype "bidirectional"))
    )
    (net (code "66") (name "Net-(U$7-M8)") (class "Default")
      (node (ref "U$27") (pin "P$1") (pinfunction "P$1_P$1") (pintype "bidirectional"))
      (node (ref "U$7") (pin "P$18") (pinfunction "M8_P$18") (pintype "bidirectional"))
    )
    (net (code "67") (name "Net-(U$7-Q1)") (class "Default")
      (node (ref "U$12") (pin "P$1") (pinfunction "P$1_P$1") (pintype "bidirectional"))
      (node (ref "U$7") (pin "P$19") (pinfunction "Q1_P$19") (pintype "bidirectional"))
    )
    (net (code "68") (name "Net-(U$7-Q2)") (class "Default")
      (node (ref "U$14") (pin "P$1") (pinfunction "P$1_P$1") (pintype "bidirectional"))
      (node (ref "U$7") (pin "P$20") (pinfunction "Q2_P$20") (pintype "bidirectional"))
    )
    (net (code "69") (name "Net-(U$7-Q3)") (class "Default")
      (node (ref "U$16") (pin "P$1") (pinfunction "P$1_P$1") (pintype "bidirectional"))
      (node (ref "U$7") (pin "P$21") (pinfunction "Q3_P$21") (pintype "bidirectional"))
    )
    (net (code "70") (name "Net-(U$7-Q4)") (class "Default")
      (node (ref "U$18") (pin "P$1") (pinfunction "P$1_P$1") (pintype "bidirectional"))
      (node (ref "U$7") (pin "P$22") (pinfunction "Q4_P$22") (pintype "bidirectional"))
    )
    (net (code "71") (name "Net-(U$7-Q5)") (class "Default")
      (node (ref "U$20") (pin "P$1") (pinfunction "P$1_P$1") (pintype "bidirectional"))
      (node (ref "U$7") (pin "P$23") (pinfunction "Q5_P$23") (pintype "bidirectional"))
    )
    (net (code "72") (name "Net-(U$7-Q6)") (class "Default")
      (node (ref "U$22") (pin "P$1") (pinfunction "P$1_P$1") (pintype "bidirectional"))
      (node (ref "U$7") (pin "P$24") (pinfunction "Q6_P$24") (pintype "bidirectional"))
    )
    (net (code "73") (name "Net-(U$7-Q7)") (class "Default")
      (node (ref "U$24") (pin "P$1") (pinfunction "P$1_P$1") (pintype "bidirectional"))
      (node (ref "U$7") (pin "P$25") (pinfunction "Q7_P$25") (pintype "bidirectional"))
    )
    (net (code "74") (name "Net-(U$7-Q8)") (class "Default")
      (node (ref "U$26") (pin "P$1") (pinfunction "P$1_P$1") (pintype "bidirectional"))
      (node (ref "U$7") (pin "P$26") (pinfunction "Q8_P$26") (pintype "bidirectional"))
    )
    (net (code "75") (name "Net-(U$60-PadP$1)") (class "Default")
      (node (ref "U$60") (pin "P$1") (pinfunction "P$1_P$1") (pintype "bidirectional"))
      (node (ref "U$61") (pin "P$1") (pinfunction "P$1_P$1") (pintype "bidirectional"))
      (node (ref "U$62") (pin "P$1") (pinfunction "P$1_P$1") (pintype "bidirectional"))
      (node (ref "U$63") (pin "P$1") (pinfunction "P$1_P$1") (pintype "bidirectional"))
      (node (ref "U$64") (pin "P$1") (pinfunction "P$1_P$1") (pintype "bidirectional"))
    )
    (net (code "76") (name "Net-(U$60-PadP$2)") (class "Default")
      (node (ref "U$60") (pin "P$2") (pinfunction "P$2_P$2") (pintype "bidirectional"))
      (node (ref "U$68") (pin "P$2") (pinfunction "P$2_P$2") (pintype "bidirectional"))
    )
    (net (code "77") (name "Net-(U$61-PadP$2)") (class "Default")
      (node (ref "U$61") (pin "P$2") (pinfunction "P$2_P$2") (pintype "bidirectional"))
      (node (ref "U$66") (pin "P$2") (pinfunction "P$2_P$2") (pintype "bidirectional"))
    )
    (net (code "78") (name "Net-(U$85-PadP$1)") (class "Default")
      (node (ref "U$85") (pin "P$1") (pinfunction "P$1_P$1") (pintype "bidirectional"))
      (node (ref "U$86") (pin "P$1") (pinfunction "P$1_P$1") (pintype "bidirectional"))
      (node (ref "U$87") (pin "P$1") (pinfunction "P$1_P$1") (pintype "bidirectional"))
    )
    (net (code "79") (name "Net-(U$90-VIN)") (class "Default")
      (node (ref "F5") (pin "1A") (pinfunction "1A_1A") (pintype "passive"))
      (node (ref "U$90") (pin "P$1") (pinfunction "VIN_P$1") (pintype "bidirectional"))
    )
    (net (code "80") (name "unconnected-(D6-PadC)") (class "Default")
      (node (ref "D6") (pin "C") (pinfunction "C_C") (pintype "passive"))
    )
    (net (code "81") (name "unconnected-(DC1-+VIN-Pad1)") (class "Default")
      (node (ref "DC1") (pin "1") (pinfunction "+VIN_1") (pintype "passive"))
    )
    (net (code "82") (name "unconnected-(DC1-+VOUT-Pad11)") (class "Default")
      (node (ref "DC1") (pin "11") (pinfunction "+VOUT_11") (pintype "passive"))
    )
    (net (code "83") (name "unconnected-(DC1--VIN-Pad12)") (class "Default")
      (node (ref "DC1") (pin "12") (pinfunction "-VIN_12") (pintype "passive"))
    )
    (net (code "84") (name "unconnected-(DC1--VOUT-Pad10)") (class "Default")
      (node (ref "DC1") (pin "10") (pinfunction "-VOUT_10") (pintype "passive"))
    )
    (net (code "85") (name "unconnected-(DC2-+VIN-Pad1)") (class "Default")
      (node (ref "DC2") (pin "1") (pinfunction "+VIN_1") (pintype "passive"))
    )
    (net (code "86") (name "unconnected-(DC2-+VOUT-Pad11)") (class "Default")
      (node (ref "DC2") (pin "11") (pinfunction "+VOUT_11") (pintype "passive"))
    )
    (net (code "87") (name "unconnected-(DC2--VIN-Pad12)") (class "Default")
      (node (ref "DC2") (pin "12") (pinfunction "-VIN_12") (pintype "passive"))
    )
    (net (code "88") (name "unconnected-(DC2--VOUT-Pad10)") (class "Default")
      (node (ref "DC2") (pin "10") (pinfunction "-VOUT_10") (pintype "passive"))
    )
    (net (code "89") (name "unconnected-(DC4-+VIN-Pad1)") (class "Default")
      (node (ref "DC4") (pin "1") (pinfunction "+VIN_1") (pintype "passive"))
    )
    (net (code "90") (name "unconnected-(DC4-+VOUT-Pad11)") (class "Default")
      (node (ref "DC4") (pin "11") (pinfunction "+VOUT_11") (pintype "passive"))
    )
    (net (code "91") (name "unconnected-(DC4--VIN-Pad12)") (class "Default")
      (node (ref "DC4") (pin "12") (pinfunction "-VIN_12") (pintype "passive"))
    )
    (net (code "92") (name "unconnected-(DC4--VOUT-Pad10)") (class "Default")
      (node (ref "DC4") (pin "10") (pinfunction "-VOUT_10") (pintype "passive"))
    )
    (net (code "93") (name "unconnected-(F1-Pad1B)") (class "Default")
      (node (ref "F1") (pin "1B") (pinfunction "1B_1B") (pintype "passive"))
    )
    (net (code "94") (name "unconnected-(F1-Pad2B)") (class "Default")
      (node (ref "F1") (pin "2B") (pinfunction "2B_2B") (pintype "passive"))
    )
    (net (code "95") (name "unconnected-(F2-Pad1B)") (class "Default")
      (node (ref "F2") (pin "1B") (pinfunction "1B_1B") (pintype "passive"))
    )
    (net (code "96") (name "unconnected-(F2-Pad2B)") (class "Default")
      (node (ref "F2") (pin "2B") (pinfunction "2B_2B") (pintype "passive"))
    )
    (net (code "97") (name "unconnected-(F3-Pad1B)") (class "Default")
      (node (ref "F3") (pin "1B") (pinfunction "1B_1B") (pintype "passive"))
    )
    (net (code "98") (name "unconnected-(F3-Pad2B)") (class "Default")
      (node (ref "F3") (pin "2B") (pinfunction "2B_2B") (pintype "passive"))
    )
    (net (code "99") (name "unconnected-(F5-Pad1B)") (class "Default")
      (node (ref "F5") (pin "1B") (pinfunction "1B_1B") (pintype "passive"))
    )
    (net (code "100") (name "unconnected-(F5-Pad2B)") (class "Default")
      (node (ref "F5") (pin "2B") (pinfunction "2B_2B") (pintype "passive"))
    )
    (net (code "101") (name "unconnected-(U$1-PadP$2)") (class "Default")
      (node (ref "U$1") (pin "P$2") (pinfunction "P$2_P$2") (pintype "bidirectional"))
    )
    (net (code "102") (name "unconnected-(U$2-PadP$2)") (class "Default")
      (node (ref "U$2") (pin "P$2") (pinfunction "P$2_P$2") (pintype "bidirectional"))
    )
    (net (code "103") (name "unconnected-(U$3-PadP$2)") (class "Default")
      (node (ref "U$3") (pin "P$2") (pinfunction "P$2_P$2") (pintype "bidirectional"))
    )
    (net (code "104") (name "unconnected-(U$4-PadP$2)") (class "Default")
      (node (ref "U$4") (pin "P$2") (pinfunction "P$2_P$2") (pintype "bidirectional"))
    )
    (net (code "105") (name "unconnected-(U$8-PadP$2)") (class "Default")
      (node (ref "U$8") (pin "P$2") (pinfunction "P$2_P$2") (pintype "bidirectional"))
    )
    (net (code "106") (name "unconnected-(U$9-PadP$2)") (class "Default")
      (node (ref "U$9") (pin "P$2") (pinfunction "P$2_P$2") (pintype "bidirectional"))
    )
    (net (code "107") (name "unconnected-(U$10-PadP$2)") (class "Default")
      (node (ref "U$10") (pin "P$2") (pinfunction "P$2_P$2") (pintype "bidirectional"))
    )
    (net (code "108") (name "unconnected-(U$11-PadP$2)") (class "Default")
      (node (ref "U$11") (pin "P$2") (pinfunction "P$2_P$2") (pintype "bidirectional"))
    )
    (net (code "109") (name "unconnected-(U$12-PadP$2)") (class "Default")
      (node (ref "U$12") (pin "P$2") (pinfunction "P$2_P$2") (pintype "bidirectional"))
    )
    (net (code "110") (name "unconnected-(U$13-PadP$2)") (class "Default")
      (node (ref "U$13") (pin "P$2") (pinfunction "P$2_P$2") (pintype "bidirectional"))
    )
    (net (code "111") (name "unconnected-(U$14-PadP$2)") (class "Default")
      (node (ref "U$14") (pin "P$2") (pinfunction "P$2_P$2") (pintype "bidirectional"))
    )
    (net (code "112") (name "unconnected-(U$15-PadP$2)") (class "Default")
      (node (ref "U$15") (pin "P$2") (pinfunction "P$2_P$2") (pintype "bidirectional"))
    )
    (net (code "113") (name "unconnected-(U$16-PadP$2)") (class "Default")
      (node (ref "U$16") (pin "P$2") (pinfunction "P$2_P$2") (pintype "bidirectional"))
    )
    (net (code "114") (name "unconnected-(U$17-PadP$2)") (class "Default")
      (node (ref "U$17") (pin "P$2") (pinfunction "P$2_P$2") (pintype "bidirectional"))
    )
    (net (code "115") (name "unconnected-(U$18-PadP$2)") (class "Default")
      (node (ref "U$18") (pin "P$2") (pinfunction "P$2_P$2") (pintype "bidirectional"))
    )
    (net (code "116") (name "unconnected-(U$19-PadP$2)") (class "Default")
      (node (ref "U$19") (pin "P$2") (pinfunction "P$2_P$2") (pintype "bidirectional"))
    )
    (net (code "117") (name "unconnected-(U$20-PadP$2)") (class "Default")
      (node (ref "U$20") (pin "P$2") (pinfunction "P$2_P$2") (pintype "bidirectional"))
    )
    (net (code "118") (name "unconnected-(U$21-PadP$2)") (class "Default")
      (node (ref "U$21") (pin "P$2") (pinfunction "P$2_P$2") (pintype "bidirectional"))
    )
    (net (code "119") (name "unconnected-(U$22-PadP$2)") (class "Default")
      (node (ref "U$22") (pin "P$2") (pinfunction "P$2_P$2") (pintype "bidirectional"))
    )
    (net (code "120") (name "unconnected-(U$23-PadP$2)") (class "Default")
      (node (ref "U$23") (pin "P$2") (pinfunction "P$2_P$2") (pintype "bidirectional"))
    )
    (net (code "121") (name "unconnected-(U$24-PadP$2)") (class "Default")
      (node (ref "U$24") (pin "P$2") (pinfunction "P$2_P$2") (pintype "bidirectional"))
    )
    (net (code "122") (name "unconnected-(U$25-PadP$2)") (class "Default")
      (node (ref "U$25") (pin "P$2") (pinfunction "P$2_P$2") (pintype "bidirectional"))
    )
    (net (code "123") (name "unconnected-(U$26-PadP$2)") (class "Default")
      (node (ref "U$26") (pin "P$2") (pinfunction "P$2_P$2") (pintype "bidirectional"))
    )
    (net (code "124") (name "unconnected-(U$27-PadP$2)") (class "Default")
      (node (ref "U$27") (pin "P$2") (pinfunction "P$2_P$2") (pintype "bidirectional"))
    )
    (net (code "125") (name "unconnected-(U$28-PadP$2)") (class "Default")
      (node (ref "U$28") (pin "P$2") (pinfunction "P$2_P$2") (pintype "bidirectional"))
    )
    (net (code "126") (name "unconnected-(U$29-PadP$2)") (class "Default")
      (node (ref "U$29") (pin "P$2") (pinfunction "P$2_P$2") (pintype "bidirectional"))
    )
    (net (code "127") (name "unconnected-(U$30-PadP$2)") (class "Default")
      (node (ref "U$30") (pin "P$2") (pinfunction "P$2_P$2") (pintype "bidirectional"))
    )
    (net (code "128") (name "unconnected-(U$31-PadP$2)") (class "Default")
      (node (ref "U$31") (pin "P$2") (pinfunction "P$2_P$2") (pintype "bidirectional"))
    )
    (net (code "129") (name "unconnected-(U$32-PadP$2)") (class "Default")
      (node (ref "U$32") (pin "P$2") (pinfunction "P$2_P$2") (pintype "bidirectional"))
    )
    (net (code "130") (name "unconnected-(U$33-PadP$2)") (class "Default")
      (node (ref "U$33") (pin "P$2") (pinfunction "P$2_P$2") (pintype "bidirectional"))
    )
    (net (code "131") (name "unconnected-(U$34-PadP$2)") (class "Default")
      (node (ref "U$34") (pin "P$2") (pinfunction "P$2_P$2") (pintype "bidirectional"))
    )
    (net (code "132") (name "unconnected-(U$35-PadP$2)") (class "Default")
      (node (ref "U$35") (pin "P$2") (pinfunction "P$2_P$2") (pintype "bidirectional"))
    )
    (net (code "133") (name "unconnected-(U$36-PadP$2)") (class "Default")
      (node (ref "U$36") (pin "P$2") (pinfunction "P$2_P$2") (pintype "bidirectional"))
    )
    (net (code "134") (name "unconnected-(U$37-PadP$2)") (class "Default")
      (node (ref "U$37") (pin "P$2") (pinfunction "P$2_P$2") (pintype "bidirectional"))
    )
    (net (code "135") (name "unconnected-(U$38-PadP$2)") (class "Default")
      (node (ref "U$38") (pin "P$2") (pinfunction "P$2_P$2") (pintype "bidirectional"))
    )
    (net (code "136") (name "unconnected-(U$39-PadP$2)") (class "Default")
      (node (ref "U$39") (pin "P$2") (pinfunction "P$2_P$2") (pintype "bidirectional"))
    )
    (net (code "137") (name "unconnected-(U$40-PadP$2)") (class "Default")
      (node (ref "U$40") (pin "P$2") (pinfunction "P$2_P$2") (pintype "bidirectional"))
    )
    (net (code "138") (name "unconnected-(U$41-PadP$2)") (class "Default")
      (node (ref "U$41") (pin "P$2") (pinfunction "P$2_P$2") (pintype "bidirectional"))
    )
    (net (code "139") (name "unconnected-(U$42-PadP$2)") (class "Default")
      (node (ref "U$42") (pin "P$2") (pinfunction "P$2_P$2") (pintype "bidirectional"))
    )
    (net (code "140") (name "unconnected-(U$43-PadP$2)") (class "Default")
      (node (ref "U$43") (pin "P$2") (pinfunction "P$2_P$2") (pintype "bidirectional"))
    )
    (net (code "141") (name "unconnected-(U$44-PadP$2)") (class "Default")
      (node (ref "U$44") (pin "P$2") (pinfunction "P$2_P$2") (pintype "bidirectional"))
    )
    (net (code "142") (name "unconnected-(U$45-PadP$2)") (class "Default")
      (node (ref "U$45") (pin "P$2") (pinfunction "P$2_P$2") (pintype "bidirectional"))
    )
    (net (code "143") (name "unconnected-(U$46-PadP$2)") (class "Default")
      (node (ref "U$46") (pin "P$2") (pinfunction "P$2_P$2") (pintype "bidirectional"))
    )
    (net (code "144") (name "unconnected-(U$47-PadP$2)") (class "Default")
      (node (ref "U$47") (pin "P$2") (pinfunction "P$2_P$2") (pintype "bidirectional"))
    )
    (net (code "145") (name "unconnected-(U$48-PadP$2)") (class "Default")
      (node (ref "U$48") (pin "P$2") (pinfunction "P$2_P$2") (pintype "bidirectional"))
    )
    (net (code "146") (name "unconnected-(U$49-PadP$2)") (class "Default")
      (node (ref "U$49") (pin "P$2") (pinfunction "P$2_P$2") (pintype "bidirectional"))
    )
    (net (code "147") (name "unconnected-(U$50-PadP$2)") (class "Default")
      (node (ref "U$50") (pin "P$2") (pinfunction "P$2_P$2") (pintype "bidirectional"))
    )
    (net (code "148") (name "unconnected-(U$51-PadP$2)") (class "Default")
      (node (ref "U$51") (pin "P$2") (pinfunction "P$2_P$2") (pintype "bidirectional"))
    )
    (net (code "149") (name "unconnected-(U$52-PadP$2)") (class "Default")
      (node (ref "U$52") (pin "P$2") (pinfunction "P$2_P$2") (pintype "bidirectional"))
    )
    (net (code "150") (name "unconnected-(U$53-PadP$2)") (class "Default")
      (node (ref "U$53") (pin "P$2") (pinfunction "P$2_P$2") (pintype "bidirectional"))
    )
    (net (code "151") (name "unconnected-(U$54-PadP$2)") (class "Default")
      (node (ref "U$54") (pin "P$2") (pinfunction "P$2_P$2") (pintype "bidirectional"))
    )
    (net (code "152") (name "unconnected-(U$55-PadP$2)") (class "Default")
      (node (ref "U$55") (pin "P$2") (pinfunction "P$2_P$2") (pintype "bidirectional"))
    )
    (net (code "153") (name "unconnected-(U$56-PadP$2)") (class "Default")
      (node (ref "U$56") (pin "P$2") (pinfunction "P$2_P$2") (pintype "bidirectional"))
    )
    (net (code "154") (name "unconnected-(U$57-PadP$2)") (class "Default")
      (node (ref "U$57") (pin "P$2") (pinfunction "P$2_P$2") (pintype "bidirectional"))
    )
    (net (code "155") (name "unconnected-(U$58-PadP$2)") (class "Default")
      (node (ref "U$58") (pin "P$2") (pinfunction "P$2_P$2") (pintype "bidirectional"))
    )
    (net (code "156") (name "unconnected-(U$59-PadP$2)") (class "Default")
      (node (ref "U$59") (pin "P$2") (pinfunction "P$2_P$2") (pintype "bidirectional"))
    )
    (net (code "157") (name "unconnected-(U$71-PadP$2)") (class "Default")
      (node (ref "U$71") (pin "P$2") (pinfunction "P$2_P$2") (pintype "bidirectional"))
    )
    (net (code "158") (name "unconnected-(U$72-PadP$2)") (class "Default")
      (node (ref "U$72") (pin "P$2") (pinfunction "P$2_P$2") (pintype "bidirectional"))
    )
    (net (code "159") (name "unconnected-(U$73-PadP$2)") (class "Default")
      (node (ref "U$73") (pin "P$2") (pinfunction "P$2_P$2") (pintype "bidirectional"))
    )
    (net (code "160") (name "unconnected-(U$74-PadP$2)") (class "Default")
      (node (ref "U$74") (pin "P$2") (pinfunction "P$2_P$2") (pintype "bidirectional"))
    )
    (net (code "161") (name "unconnected-(U$75-PadP$2)") (class "Default")
      (node (ref "U$75") (pin "P$2") (pinfunction "P$2_P$2") (pintype "bidirectional"))
    )
    (net (code "162") (name "unconnected-(U$76-PadP$2)") (class "Default")
      (node (ref "U$76") (pin "P$2") (pinfunction "P$2_P$2") (pintype "bidirectional"))
    )
    (net (code "163") (name "unconnected-(U$77-PadP$2)") (class "Default")
      (node (ref "U$77") (pin "P$2") (pinfunction "P$2_P$2") (pintype "bidirectional"))
    )
    (net (code "164") (name "unconnected-(U$78-PadP$2)") (class "Default")
      (node (ref "U$78") (pin "P$2") (pinfunction "P$2_P$2") (pintype "bidirectional"))
    )
    (net (code "165") (name "unconnected-(U$79-PadP$2)") (class "Default")
      (node (ref "U$79") (pin "P$2") (pinfunction "P$2_P$2") (pintype "bidirectional"))
    )
  )
)
